# ultraWAPIv0_1.net
KiCad netlist of a schematic drawn in EAGLE
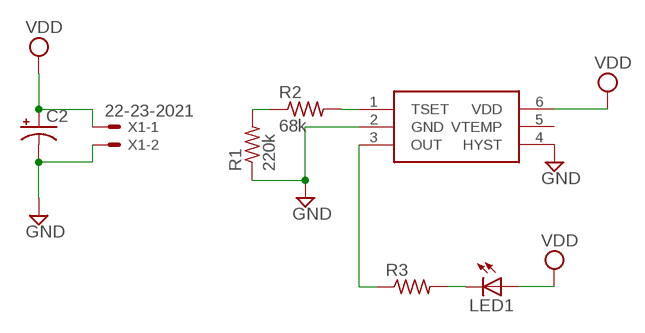
[diagram p0: schematic, sheet 1]

(export (version "E")
  (design (tool "Eeschema 10.0.6"))
  (components
    (comp (ref "C2")
      (value "CPOL-USE5-13")
      (footprint "eagle-import:E5-13")
      (libsource (lib "eagle-import") (part "CPOL-USE5-13"))
    )
    (comp (ref "LED1")
      (value "LEDCHIP-LED0603")
      (footprint "eagle-import:CHIP-LED0603")
      (libsource (lib "eagle-import") (part "LEDCHIP-LED0603"))
    )
    (comp (ref "R1")
      (value "220k")
      (footprint "eagle-import:R0603")
      (libsource (lib "eagle-import") (part "R-US_R0603"))
    )
    (comp (ref "R2")
      (value "68k")
      (footprint "eagle-import:R0603")
      (libsource (lib "eagle-import") (part "R-US_R0603"))
    )
    (comp (ref "R3")
      (value "R-US_R0603")
      (footprint "eagle-import:R0603")
      (libsource (lib "eagle-import") (part "resistor_R-US_R0603"))
    )
    (comp (ref "U$1")
      (value "TMP300B")
      (footprint "eagle-import:TSOT23-6_DDC")
      (libsource (lib "eagle-import") (part "TMP300B"))
    )
    (comp (ref "X1")
      (value "22-23-2021")
      (footprint "eagle-import:22-23-2021")
      (fields (field (name "MF") "MOLEX"))
      (libsource (lib "eagle-import") (part "22-23-2021"))
    )
  )
  (nets
    (net (code "1") (name "GND") (class "Default")
      (node (ref "C2") (pin "-") (pinfunction "-_-") (pintype "passive"))
      (node (ref "R1") (pin "1") (pinfunction "1_1") (pintype "passive"))
      (node (ref "U$1") (pin "2") (pinfunction "GND_2") (pintype "bidirectional"))
      (node (ref "U$1") (pin "4") (pinfunction "HYST_4") (pintype "bidirectional"))
      (node (ref "X1") (pin "2") (pinfunction "S_2") (pintype "passive"))
    )
    (net (code "2") (name "Net-(LED1-PadC)") (class "Default")
      (node (ref "LED1") (pin "C") (pinfunction "C_C") (pintype "passive"))
      (node (ref "R3") (pin "2") (pinfunction "2_2") (pintype "passive"))
    )
    (net (code "3") (name "Net-(R1-Pad2)") (class "Default")
      (node (ref "R1") (pin "2") (pinfunction "2_2") (pintype "passive"))
      (node (ref "R2") (pin "1") (pinfunction "1_1") (pintype "passive"))
    )
    (net (code "4") (name "Net-(U$1-OUT)") (class "Default")
      (node (ref "R3") (pin "1") (pinfunction "1_1") (pintype "passive"))
      (node (ref "U$1") (pin "3") (pinfunction "OUT_3") (pintype "bidirectional"))
    )
    (net (code "5") (name "Net-(U$1-TSET)") (class "Default")
      (node (ref "R2") (pin "2") (pinfunction "2_2") (pintype "passive"))
      (node (ref "U$1") (pin "1") (pinfunction "TSET_1") (pintype "bidirectional"))
    )
    (net (code "6") (name "VDD") (class "Default")
      (node (ref "C2") (pin "+") (pinfunction "+_+") (pintype "passive"))
      (node (ref "LED1") (pin "A") (pinfunction "A_A") (pintype "passive"))
      (node (ref "U$1") (pin "6") (pinfunction "VDD_6") (pintype "bidirectional"))
      (node (ref "X1") (pin "1") (pinfunction "S_1") (pintype "passive"))
    )
    (net (code "7") (name "unconnected-(U$1-VTEMP-Pad5)") (class "Default")
      (node (ref "U$1") (pin "5") (pinfunction "VTEMP_5") (pintype "bidirectional"))
    )
  )
)
